# ProProject_ESP32-S3_Brewpiless_V1_Rev_1_.net
KiCad netlist of a schematic drawn in EasyEDA Pro
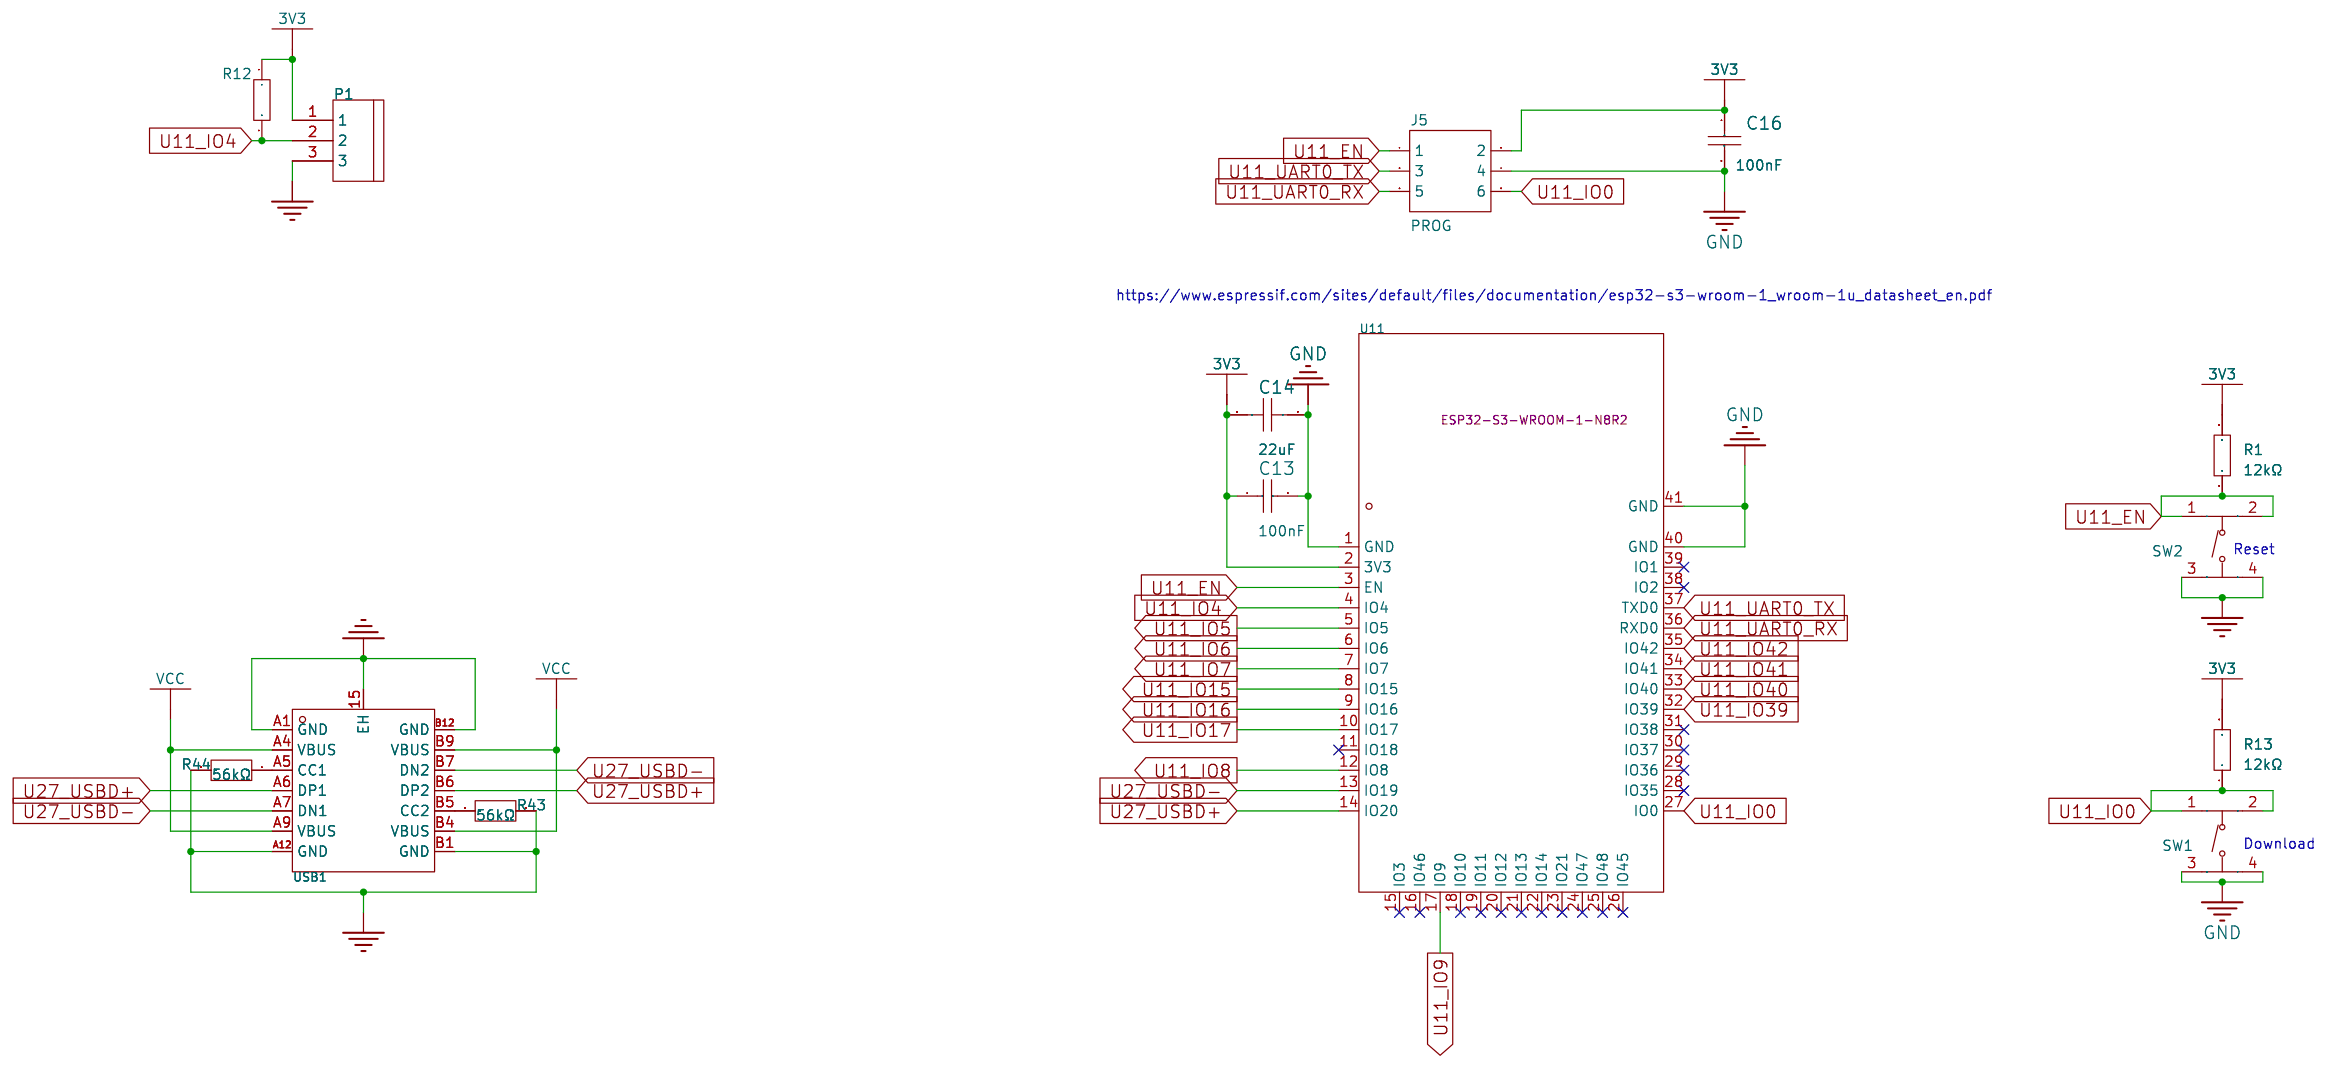
[diagram p0: ESP32]
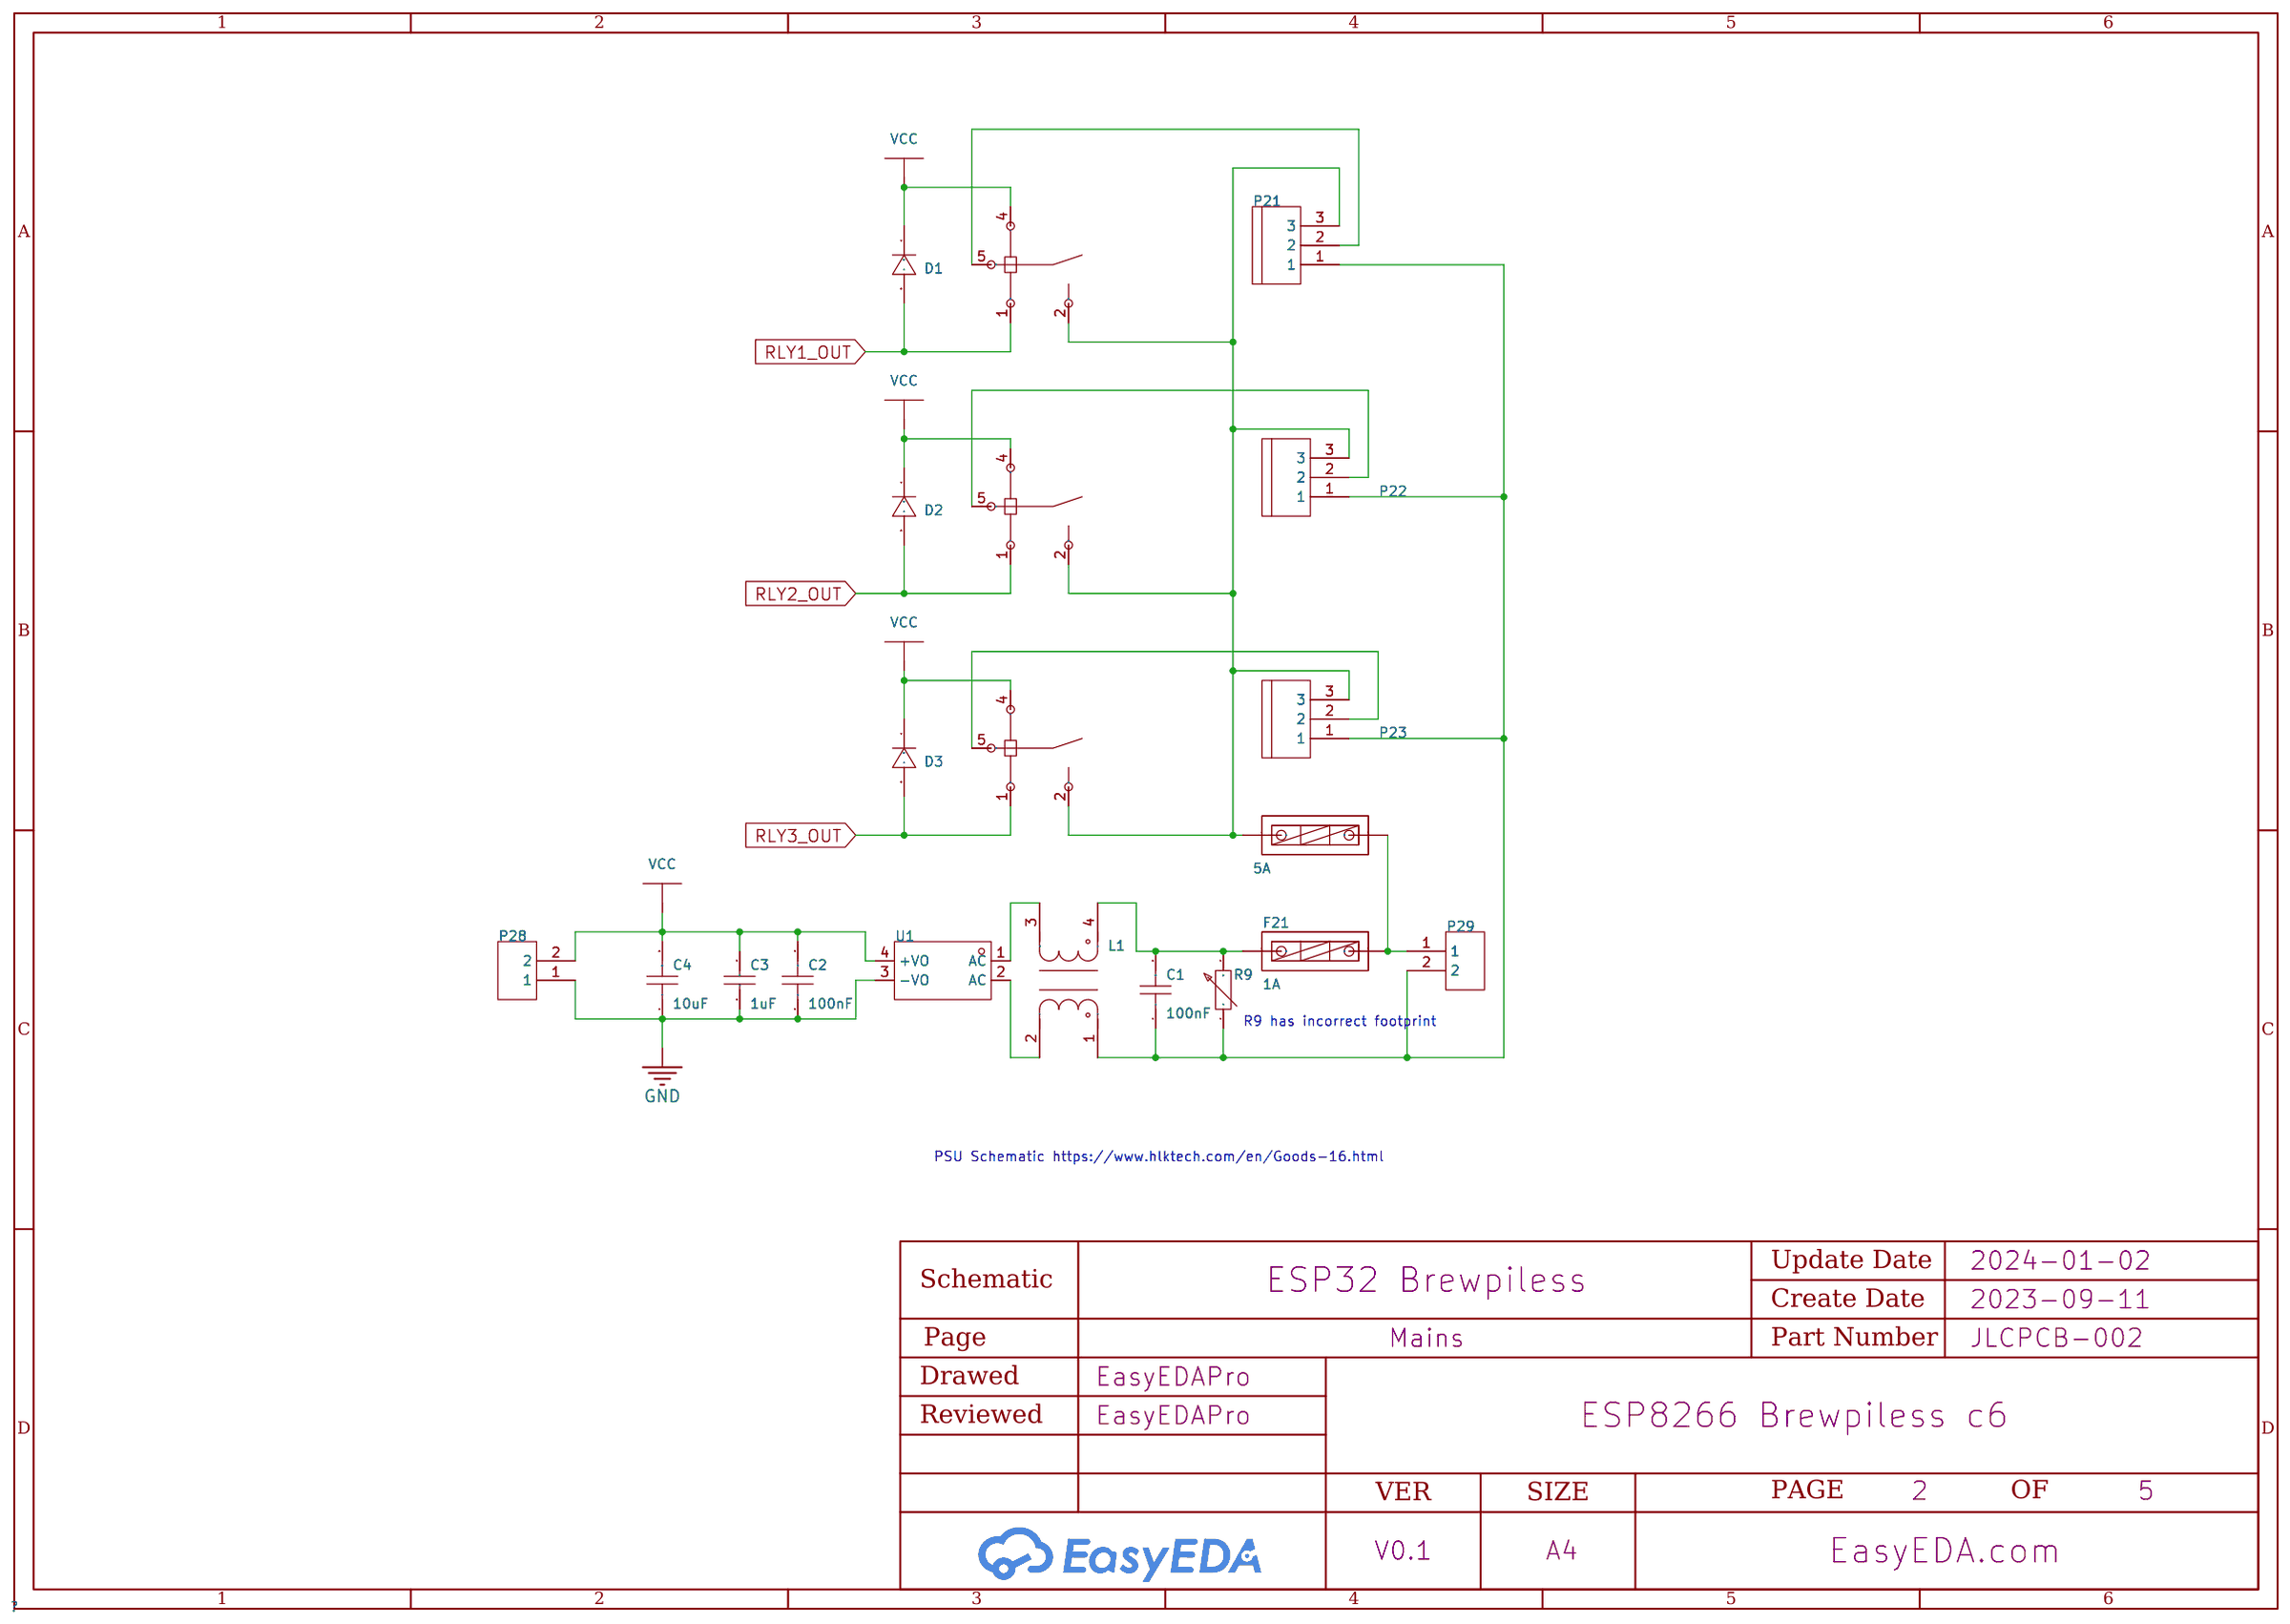
[diagram p1: Mains]
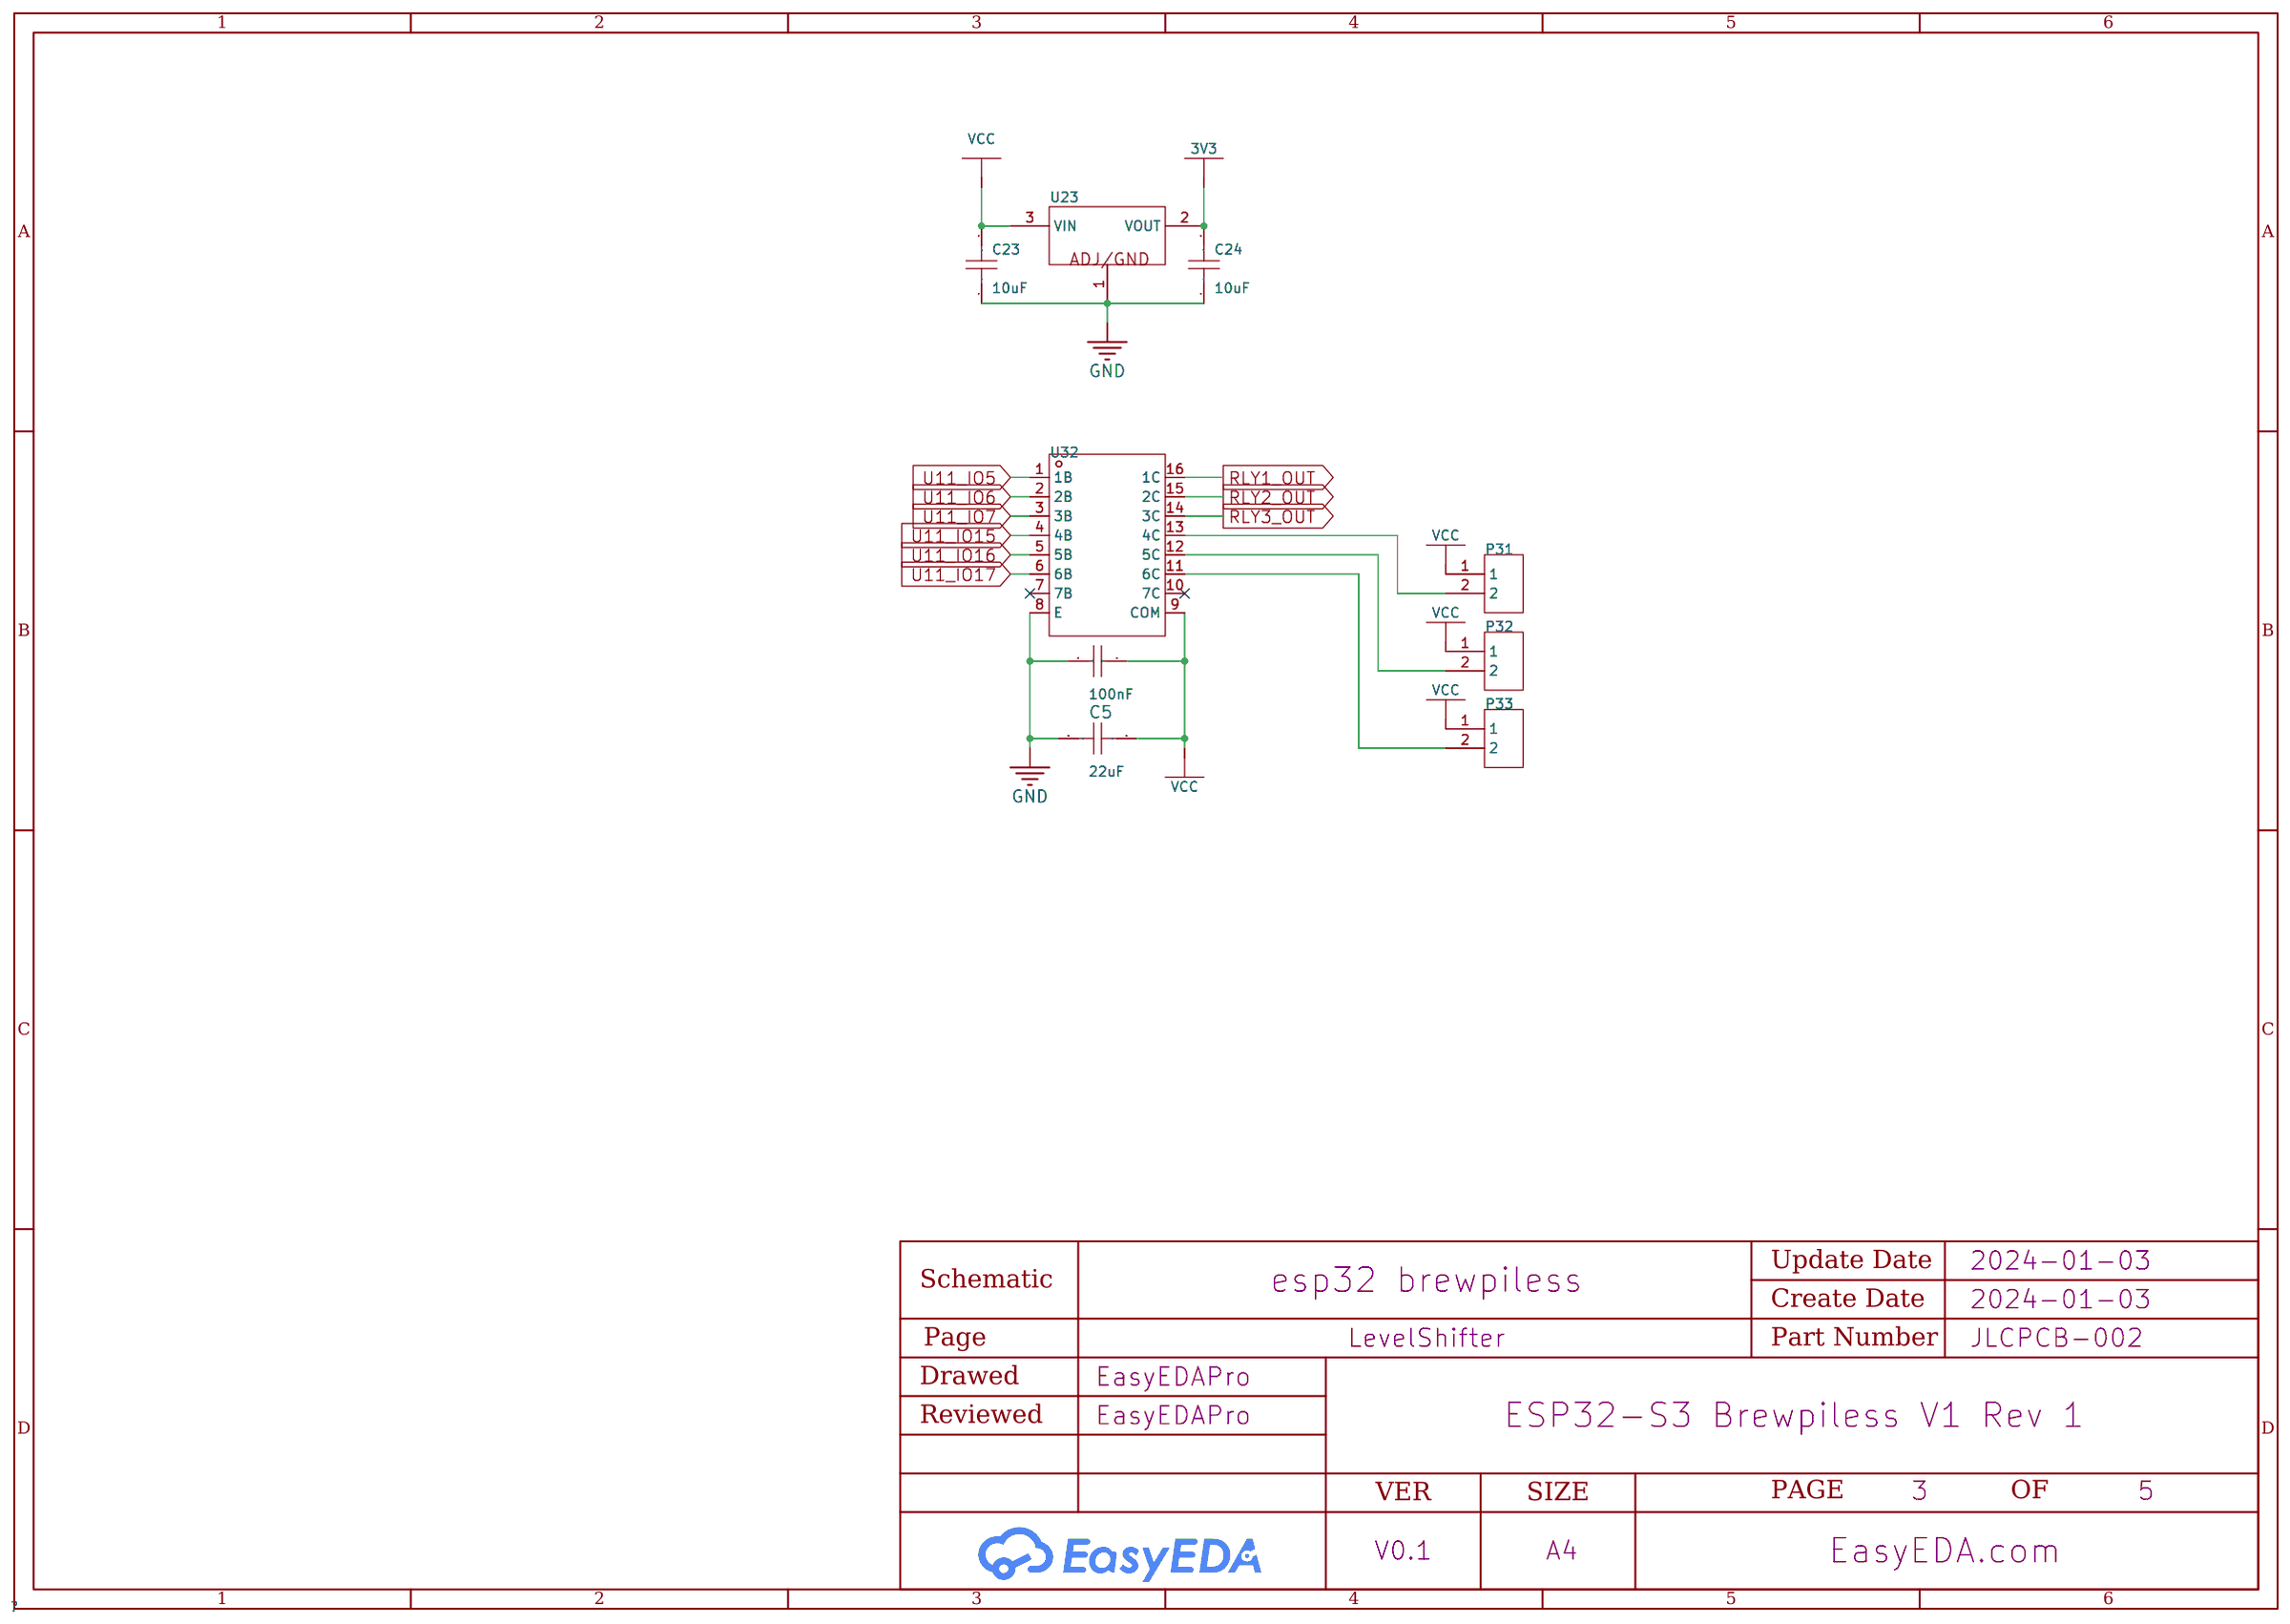
[diagram p2: LevelShifter]
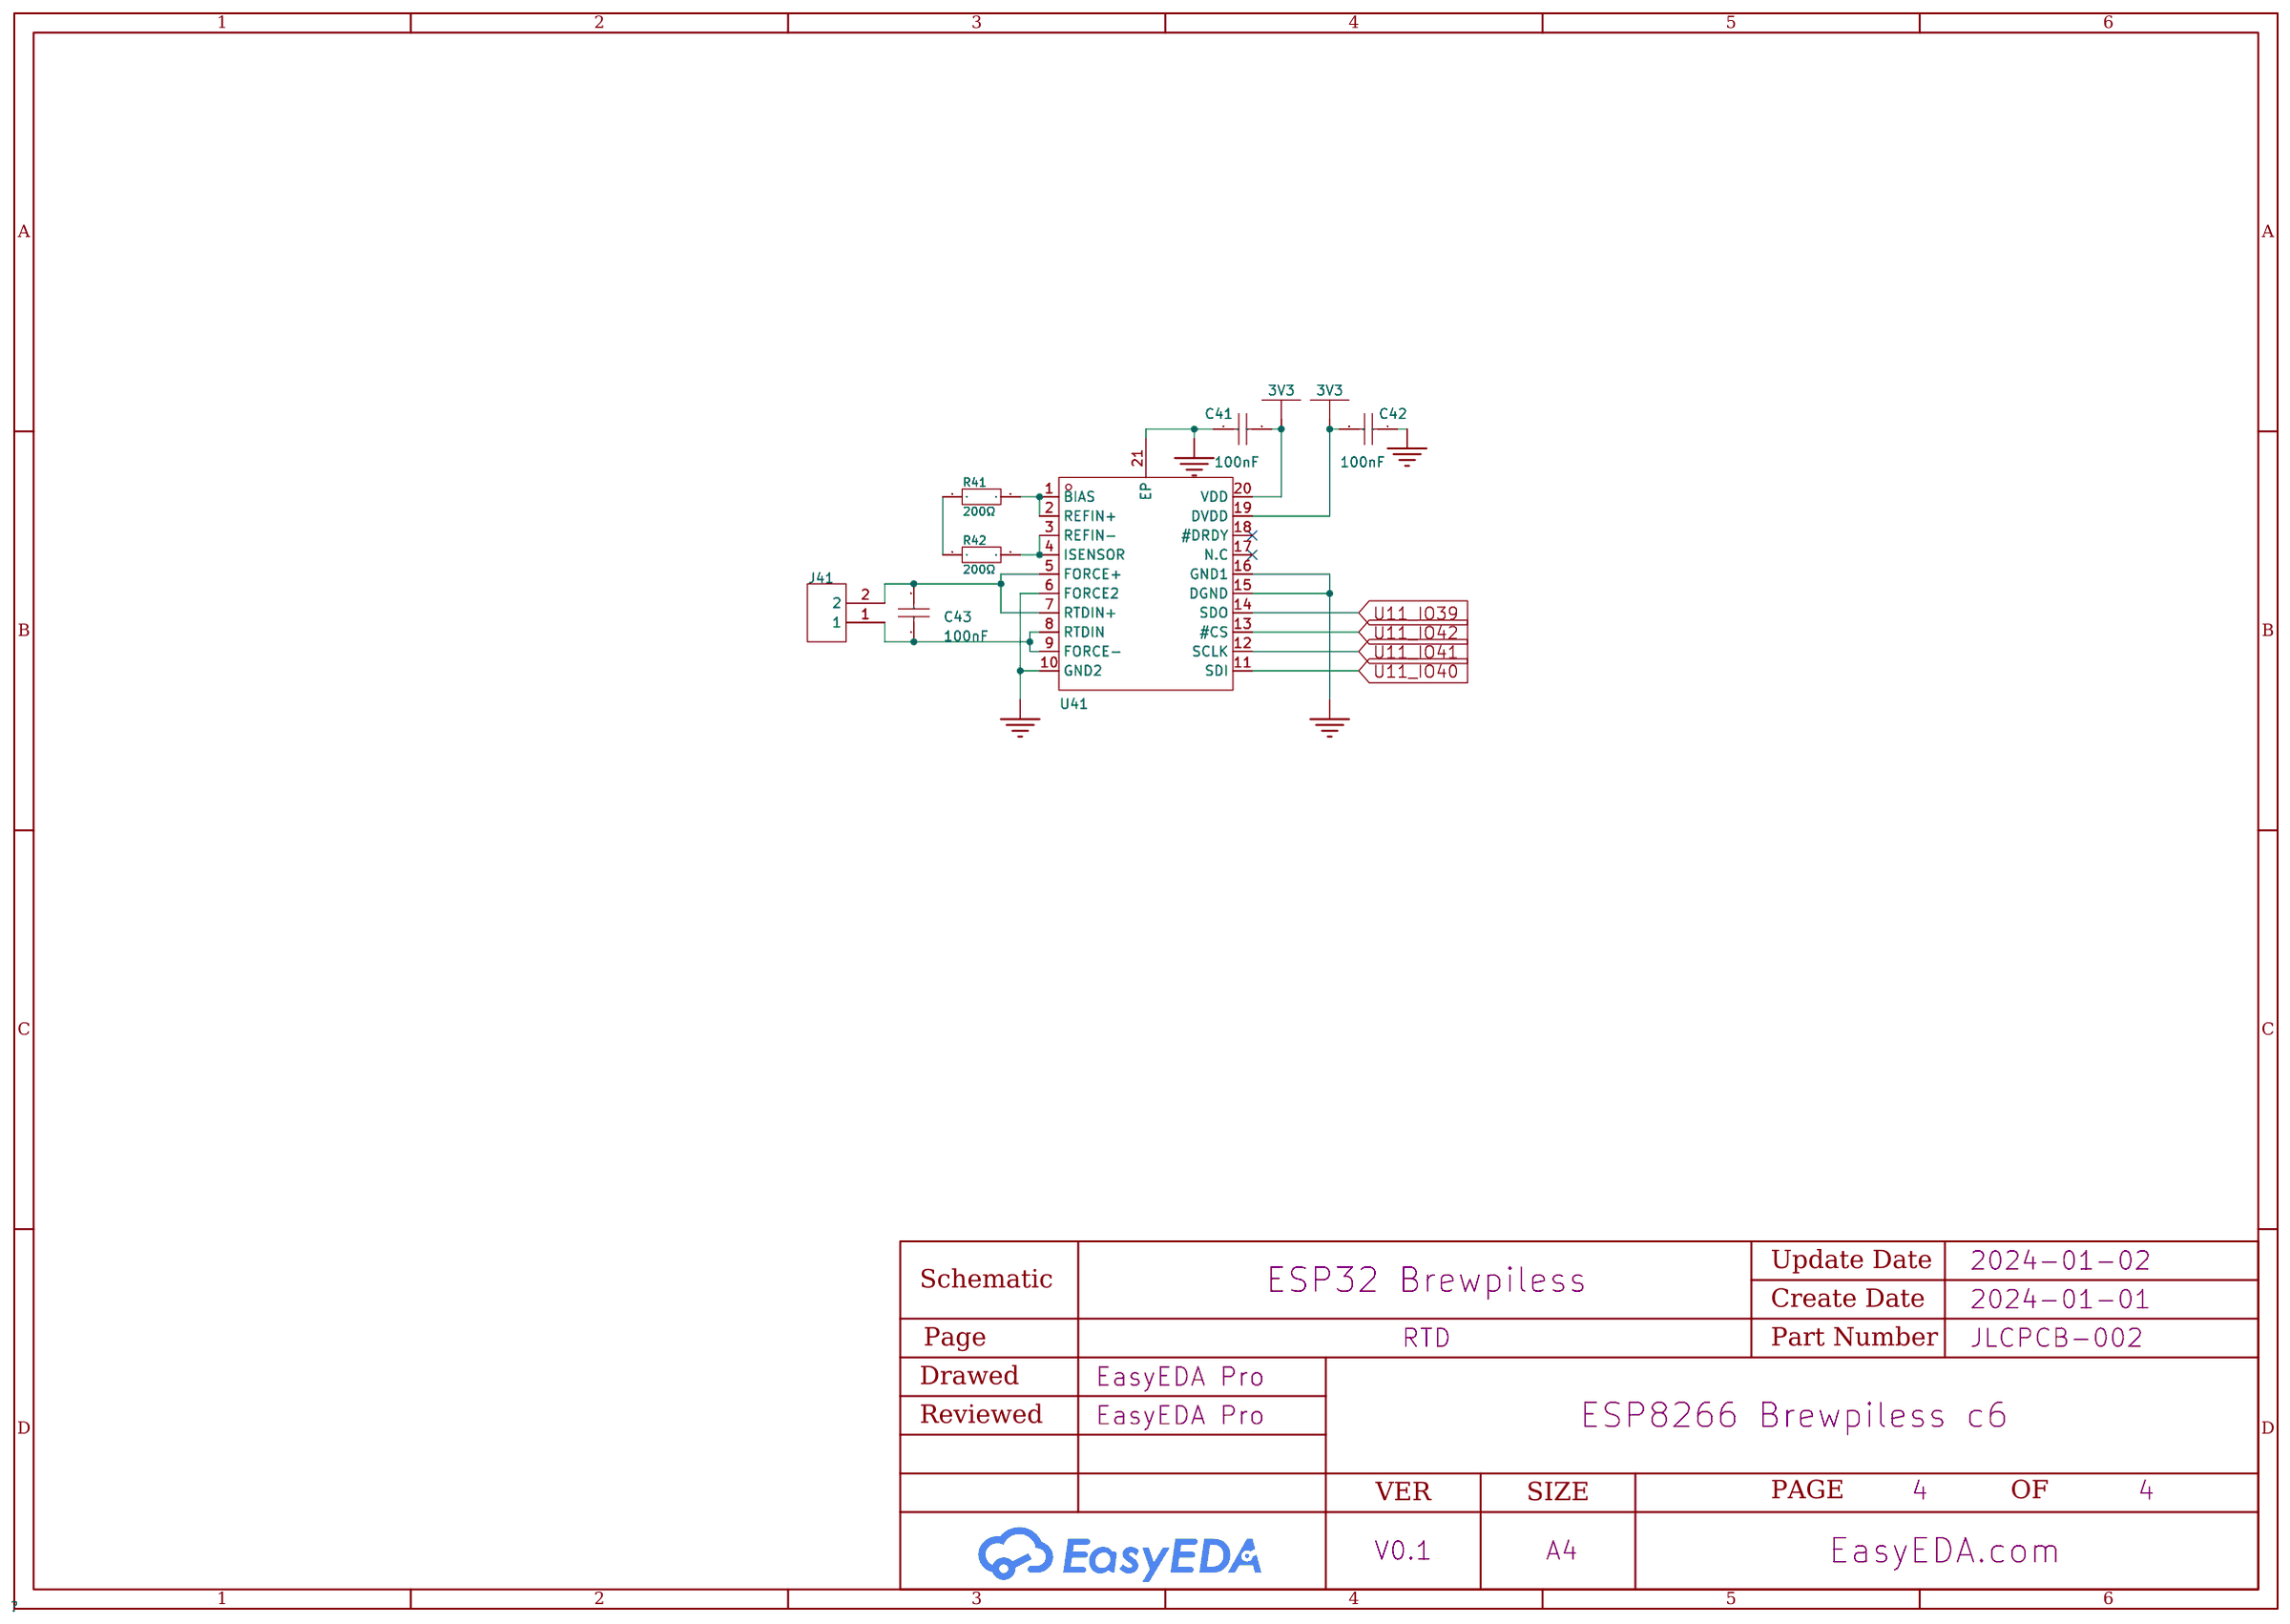
[diagram p3: RTD]
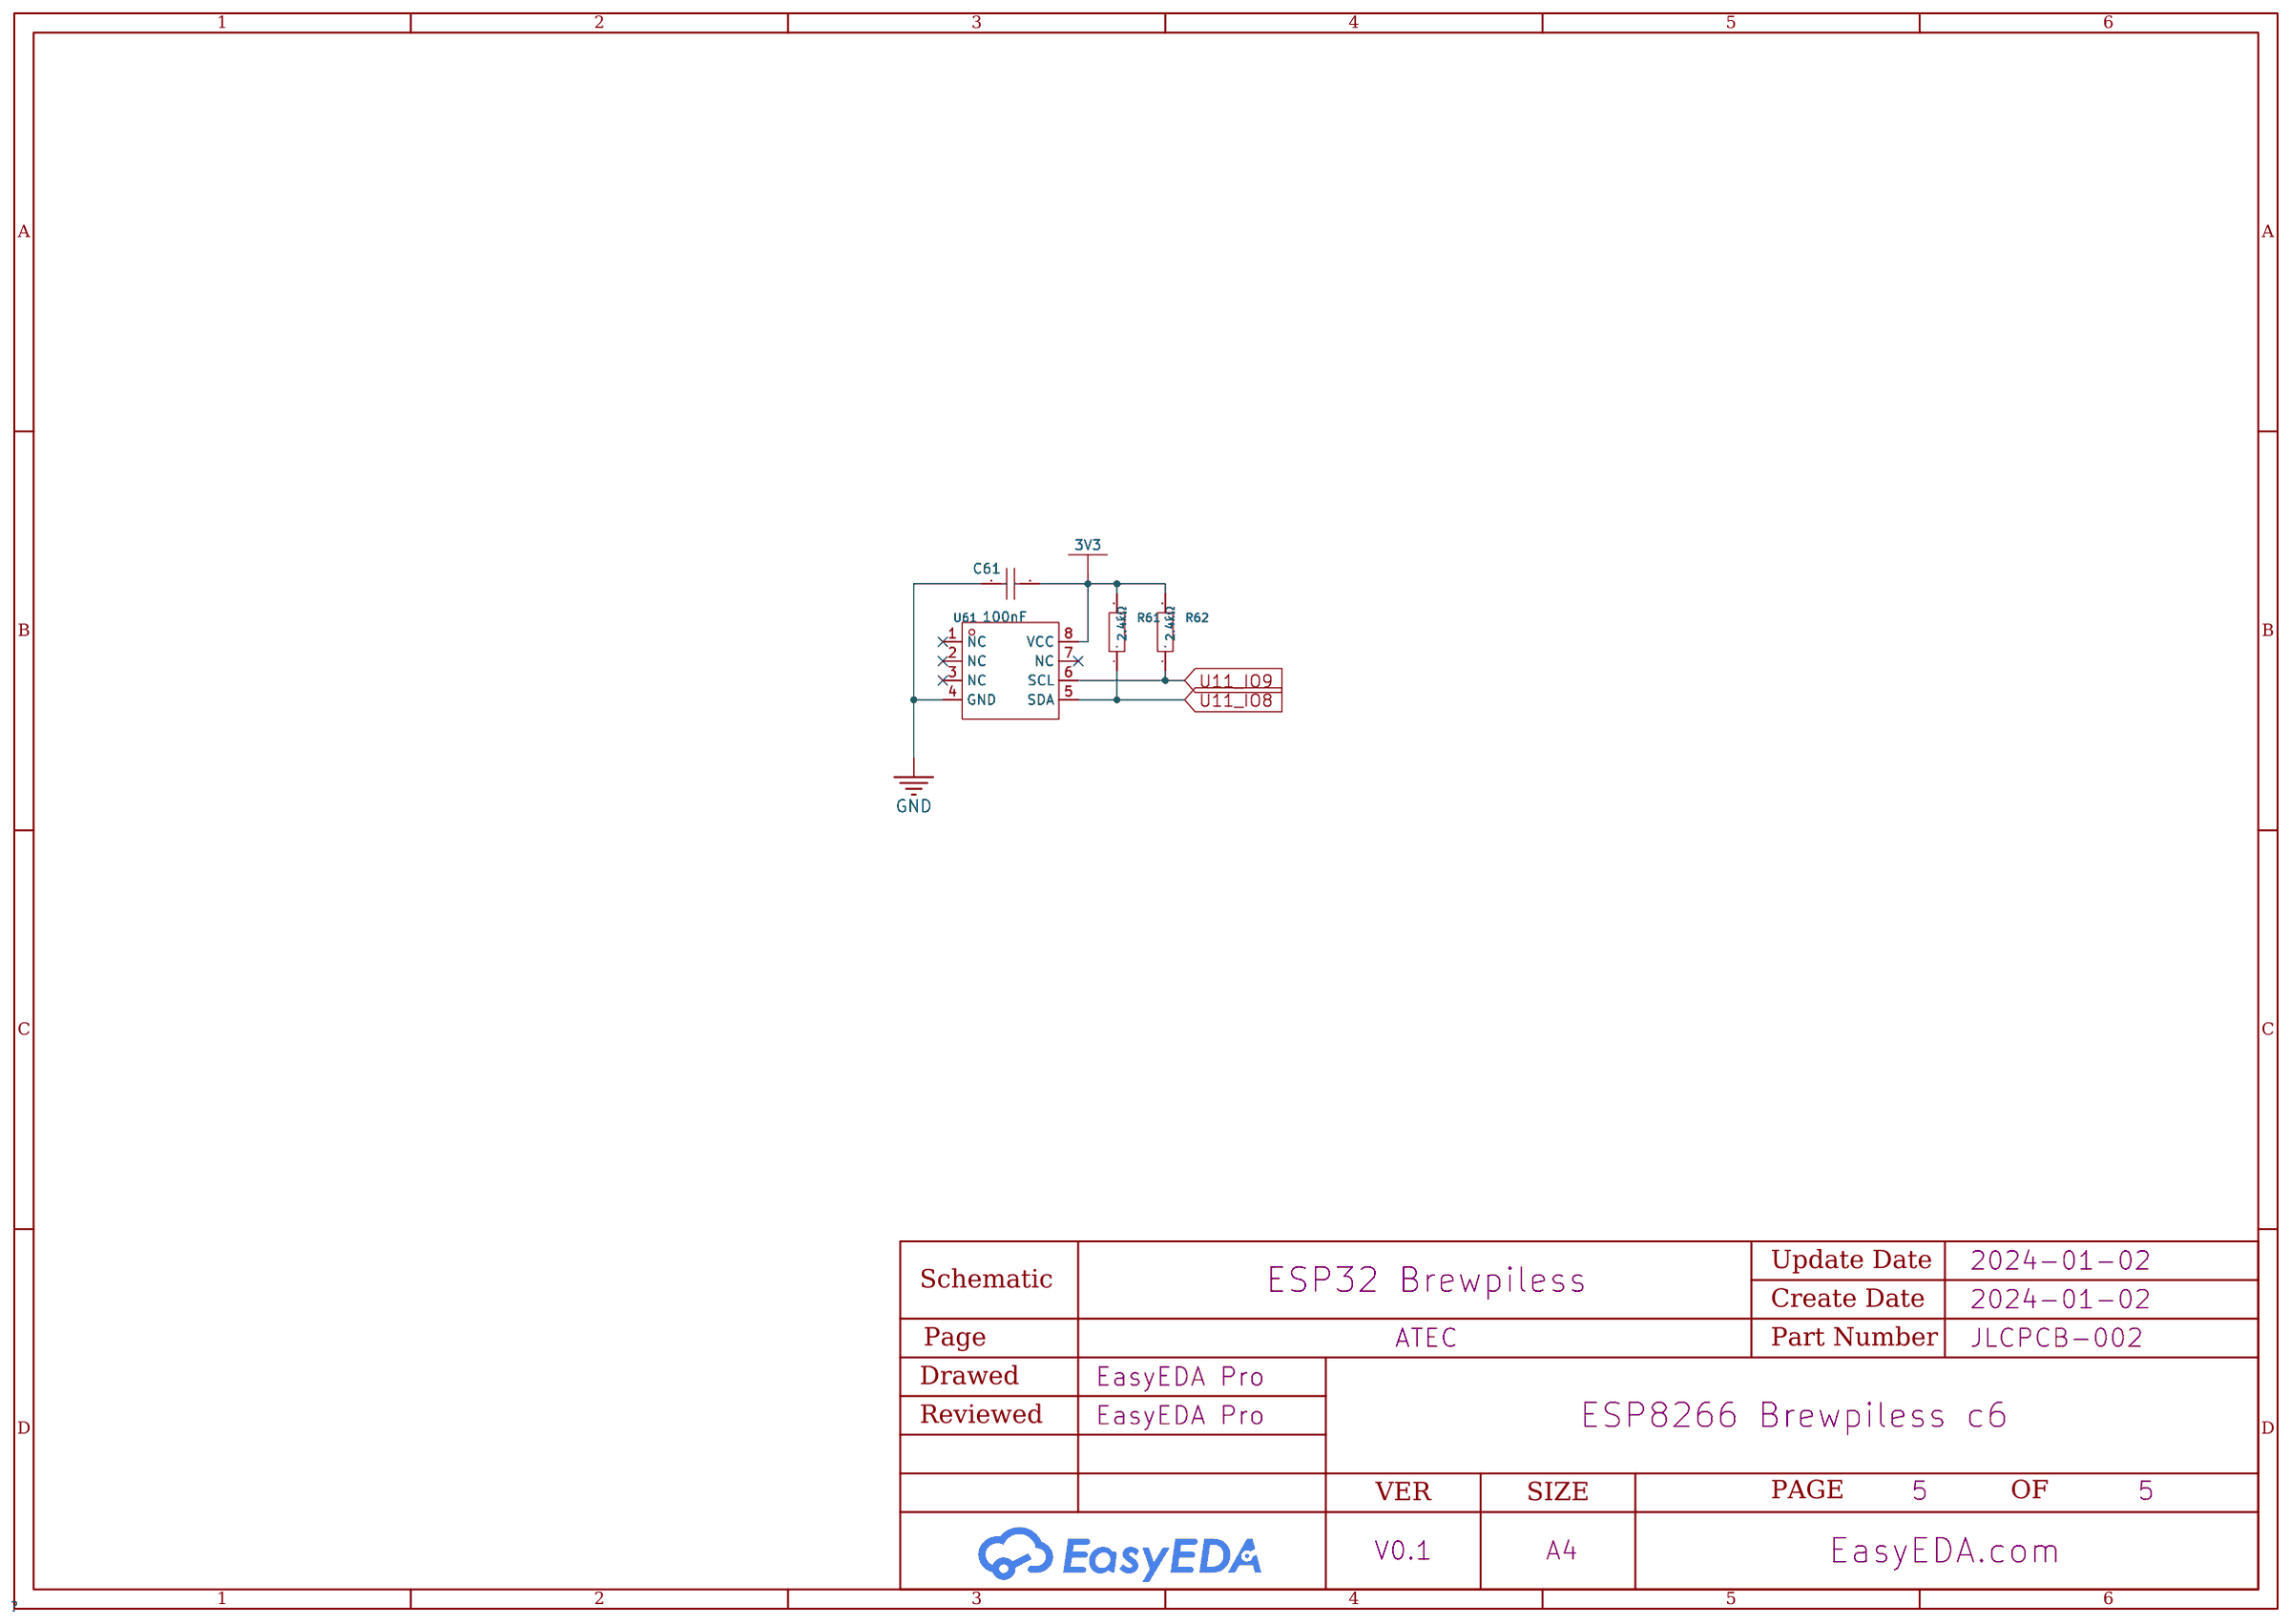
[diagram p4: ATEC]

(export (version "E")
  (design (tool "Eeschema 10.0.6"))
  (components
    (comp (ref "C13")
      (value "100nF")
      (footprint "easyedapro:C0805")
      (fields
        (field (name "Manufacturer Part") "CC0805KRX7R9BB104")
        (field (name "Manufacturer") "YAGEO(国巨)")
      )
      (libsource (lib "easyedapro") (part "CC0805KRX7R9BB104"))
    )
    (comp (ref "C14")
      (value "22uF")
      (footprint "easyedapro:C0805")
      (fields
        (field (name "Manufacturer Part") "CL21A226MAQNNNE")
        (field (name "Manufacturer") "SAMSUNG(三星)")
      )
      (libsource (lib "easyedapro") (part "CL21A226MAQNNNE"))
    )
    (comp (ref "C16")
      (value "100nF")
      (footprint "easyedapro:C0805")
      (fields
        (field (name "Manufacturer Part") "CC0805KRX7R9BB104")
        (field (name "Manufacturer") "YAGEO(国巨)")
      )
      (libsource (lib "easyedapro") (part "CC0805KRX7R9BB104"))
    )
    (comp (ref "J5")
      (value "PROG")
      (footprint "easyedapro:IDC-TH_6P-P2.54_C11214")
      (fields (field (name "Manufacturer Part") "2.54-2*3P简牛") (field (name "Manufacturer") "BOOMELE(博穆精密)"))
      (libsource (lib "easyedapro") (part "HDR-IDC-2.54-2X3P"))
    )
    (comp (ref "P1")
      (value "WJ500V-5.08-3P")
      (footprint "easyedapro:CONN-TH_3P-P5.00_WJ500V-5.08-3P")
      (fields (field (name "Manufacturer") "KANGNEX(康奈克斯电气)"))
      (libsource (lib "easyedapro") (part "WJ500V-5.08-3P-14-00A"))
    )
    (comp (ref "R1")
      (value "12kΩ")
      (footprint "easyedapro:R0805")
      (fields
        (field (name "Manufacturer Part") "0805W8F1202T5E")
        (field (name "Manufacturer") "UNI-ROYAL(厚声)")
      )
      (libsource (lib "easyedapro") (part "0805W8F1202T5E"))
    )
    (comp (ref "R12")
      (value "4.7kΩ")
      (footprint "easyedapro:R0805")
      (fields
        (field (name "Manufacturer Part") "0805W8F4701T5E")
        (field (name "Manufacturer") "UNI-ROYAL(厚声)")
      )
      (libsource (lib "easyedapro") (part "0805W8F4701T5E"))
    )
    (comp (ref "R13")
      (value "12kΩ")
      (footprint "easyedapro:R0805")
      (fields
        (field (name "Manufacturer Part") "0805W8F1202T5E")
        (field (name "Manufacturer") "UNI-ROYAL(厚声)")
      )
      (libsource (lib "easyedapro") (part "0805W8F1202T5E"))
    )
    (comp (ref "R43")
      (value "56kΩ")
      (footprint "easyedapro:R0805")
      (fields (field (name "Manufacturer Part") "ARG05DTC5602") (field (name "Manufacturer") "Viking(光颉)"))
      (libsource (lib "easyedapro") (part "ARG05DTC5602"))
    )
    (comp (ref "R44")
      (value "56kΩ")
      (footprint "easyedapro:R0805")
      (fields (field (name "Manufacturer Part") "ARG05DTC5602") (field (name "Manufacturer") "Viking(光颉)"))
      (libsource (lib "easyedapro") (part "ARG05DTC5602"))
    )
    (comp (ref "SW1")
      (value "TS-1187A-B-A-B")
      (footprint "easyedapro:SW-SMD_4P-L5.1-W5.1-P3.70-LS6.5-TL-2")
      (fields (field (name "Manufacturer") "XKB Connectivity(中国星坤)"))
      (libsource (lib "easyedapro") (part "TS-1187A-B-A-B"))
    )
    (comp (ref "SW2")
      (value "TS-1187A-B-A-B")
      (footprint "easyedapro:SW-SMD_4P-L5.1-W5.1-P3.70-LS6.5-TL-2")
      (fields (field (name "Manufacturer") "XKB Connectivity(中国星坤)"))
      (libsource (lib "easyedapro") (part "TS-1187A-B-A-B"))
    )
    (comp (ref "U11")
      (value "2.4GHz")
      (footprint "easyedapro:WIRELM-SMD_ESP32-S3-WROOM-1")
      (description "Core Processor:ESP32-S3芯片 Support Interface:I2C；GPIO；SPI；PWM；ADC；UART；USB；I2S Frequency:2.4GHz")
      (fields
        (field (name "Manufacturer Part") "ESP32-S3-WROOM-1-N8R2")
        (field (name "Manufacturer") "ESPRESSIF(乐鑫)")
      )
      (libsource (lib "easyedapro") (part "ESP32-S3-WROOM-1(N8R2)"))
    )
    (comp (ref "USB1")
      (value "TYPE-C 14P LTH10.0")
      (footprint "easyedapro:TYPE-C-SMD_918-468K2029Y50001")
      (fields (field (name "Manufacturer") "SHOU HAN(首韩)"))
      (libsource (lib "easyedapro") (part "TYPE-C 14P LTH10.0"))
    )
    (comp (ref "C1")
      (value "100nF")
      (footprint "easyedapro:CAP-TH_L12.0-W5.5-P10.00-D0.6")
      (fields
        (field (name "Manufacturer Part") "MPP104J2W10AJ22620")
        (field (name "Manufacturer") "KNSCHA(科尼盛)")
      )
      (libsource (lib "easyedapro") (part "MPP104J2W10AJ22620"))
    )
    (comp (ref "C2")
      (value "100nF")
      (footprint "easyedapro:CAP-TH_L12.0-W5.5-P10.00-D0.6")
      (fields
        (field (name "Manufacturer Part") "MPP104J2W10AJ22620")
        (field (name "Manufacturer") "KNSCHA(科尼盛)")
      )
      (libsource (lib "easyedapro") (part "MPP104J2W10AJ22620"))
    )
    (comp (ref "C3")
      (value "1uF")
      (footprint "easyedapro:C0805")
      (fields
        (field (name "Manufacturer Part") "CL21B105KBFNNNE")
        (field (name "Manufacturer") "SAMSUNG(三星)")
      )
      (libsource (lib "easyedapro") (part "CL21B105KBFNNNE"))
    )
    (comp (ref "C4")
      (value "10uF")
      (footprint "easyedapro:C0805")
      (fields
        (field (name "Manufacturer Part") "GRM21BR61H106KE43L")
        (field (name "Manufacturer") "muRata(村田)")
      )
      (libsource (lib "easyedapro") (part "GRM21BR61H106KE43L"))
    )
    (comp (ref "D1")
      (value "SM4007PL")
      (footprint "easyedapro:SOD-123F_L2.8-W1.8-LS3.7-RD")
      (fields (field (name "Manufacturer") "MDD"))
      (libsource (lib "easyedapro") (part "SM4007PL"))
    )
    (comp (ref "D2")
      (value "SM4007PL")
      (footprint "easyedapro:SOD-123F_L2.8-W1.8-LS3.7-RD")
      (fields (field (name "Manufacturer") "MDD"))
      (libsource (lib "easyedapro") (part "SM4007PL"))
    )
    (comp (ref "D3")
      (value "SM4007PL")
      (footprint "easyedapro:SOD-123F_L2.8-W1.8-LS3.7-RD")
      (fields (field (name "Manufacturer") "MDD"))
      (libsource (lib "easyedapro") (part "SM4007PL"))
    )
    (comp (ref "F21")
      (value "~")
      (footprint "easyedapro:FUSE-TH_5X20RHOSFUSECLIP-SEAT")
      (fields (field (name "Manufacturer Part") "5x20环保保险管夹/座") (field (name "Manufacturer") "xcfuse(旭程)"))
      (libsource (lib "easyedapro") (part "5x20 RHOS Fuse clip/seat"))
    )
    (comp (ref "F22")
      (value "5A")
      (footprint "easyedapro:FUSE-TH_5X20RHOSFUSECLIP-SEAT")
      (fields (field (name "Manufacturer Part") "5x20环保保险管夹/座") (field (name "Manufacturer") "xcfuse(旭程)"))
      (libsource (lib "easyedapro") (part "5x20 RHOS Fuse clip/seat"))
    )
    (comp (ref "F210")
      (value "1A")
      (footprint "easyedapro:FUSE-TH_5X20RHOSFUSECLIP-SEAT")
      (fields (field (name "Manufacturer Part") "5x20环保保险管夹/座") (field (name "Manufacturer") "xcfuse(旭程)"))
      (libsource (lib "easyedapro") (part "5x20 RHOS Fuse clip/seat"))
    )
    (comp (ref "F220")
      (value "10A")
      (footprint "easyedapro:FUSE-TH_5X20RHOSFUSECLIP-SEAT")
      (fields (field (name "Manufacturer Part") "5x20环保保险管夹/座") (field (name "Manufacturer") "xcfuse(旭程)"))
      (libsource (lib "easyedapro") (part "5x20 RHOS Fuse clip/seat"))
    )
    (comp (ref "K1")
      (value "~")
      (footprint "easyedapro:RELAY-TH_973-XXVDC-SL-A")
      (fields
        (field (name "Manufacturer Part") "973-5VDC-SL-A15A250VAC")
        (field (name "Manufacturer") "NHC(汇龙仓)")
      )
      (libsource (lib "easyedapro") (part "973-5VDC-SL-A 15A250VAC"))
    )
    (comp (ref "K2")
      (value "~")
      (footprint "easyedapro:RELAY-TH_973-XXVDC-SL-A")
      (fields
        (field (name "Manufacturer Part") "973-5VDC-SL-A15A250VAC")
        (field (name "Manufacturer") "NHC(汇龙仓)")
      )
      (libsource (lib "easyedapro") (part "973-5VDC-SL-A 15A250VAC"))
    )
    (comp (ref "K3")
      (value "~")
      (footprint "easyedapro:RELAY-TH_973-XXVDC-SL-A")
      (fields
        (field (name "Manufacturer Part") "973-5VDC-SL-A15A250VAC")
        (field (name "Manufacturer") "NHC(汇龙仓)")
      )
      (libsource (lib "easyedapro") (part "973-5VDC-SL-A 15A250VAC"))
    )
    (comp (ref "L1")
      (value "~")
      (footprint "easyedapro:FILTER-TH_UU10.5Y-10MH")
      (description "Number of Lines:2 Inductance @ Frequency:10mH@1kHz DC Resistance (DCR):750mΩ")
      (fields (field (name "Manufacturer Part") "UU10.5Y-10mH") (field (name "Manufacturer") "FH(风华)"))
      (libsource (lib "easyedapro") (part "UU10.5Y-10mH"))
    )
    (comp (ref "P21")
      (value "WJ500V-5.08-3P")
      (footprint "easyedapro:CONN-TH_3P-P5.00_WJ500V-5.08-3P")
      (fields (field (name "Manufacturer") "KANGNEX(康奈克斯电气)"))
      (libsource (lib "easyedapro") (part "WJ500V-5.08-3P-14-00A"))
    )
    (comp (ref "P22")
      (value "WJ500V-5.08-3P")
      (footprint "easyedapro:CONN-TH_3P-P5.00_WJ500V-5.08-3P")
      (fields (field (name "Manufacturer") "KANGNEX(康奈克斯电气)"))
      (libsource (lib "easyedapro") (part "WJ500V-5.08-3P-14-00A"))
    )
    (comp (ref "P23")
      (value "WJ500V-5.08-3P")
      (footprint "easyedapro:CONN-TH_3P-P5.00_WJ500V-5.08-3P")
      (fields (field (name "Manufacturer") "KANGNEX(康奈克斯电气)"))
      (libsource (lib "easyedapro") (part "WJ500V-5.08-3P-14-00A"))
    )
    (comp (ref "P28")
      (value "WJ500V-5.08-2P")
      (footprint "easyedapro:CONN-TH_2P-P5.00_WJ500V-5.08-2P")
      (fields (field (name "Manufacturer") "KANGNEX(康奈克斯电气)"))
      (libsource (lib "easyedapro") (part "WJ500V-5.08-2P-14-00A"))
    )
    (comp (ref "P29")
      (value "WJ500V-5.08-2P")
      (footprint "easyedapro:CONN-TH_2P-P5.00_WJ500V-5.08-2P")
      (fields (field (name "Manufacturer") "KANGNEX(康奈克斯电气)"))
      (libsource (lib "easyedapro") (part "WJ500V-5.08-2P-14-00A"))
    )
    (comp (ref "R9")
      (value "10D561K")
      (footprint "easyedapro:RES-TH_L13.0-W6.0-P7.50-D0.9-S6.00")
      (fields (field (name "Manufacturer") "HEL(鸿志)"))
      (libsource (lib "easyedapro") (part "10D561K"))
    )
    (comp (ref "U1")
      (value "~")
      (footprint "easyedapro:PWRM-TH_HLK-5M05")
      (fields (field (name "Manufacturer Part") "HLK-5M05") (field (name "Manufacturer") "HI-LINK(海凌科)"))
      (libsource (lib "easyedapro") (part "HLK-5M05"))
    )
    (comp (ref "C5")
      (value "22uF")
      (footprint "easyedapro:C0805")
      (fields
        (field (name "Manufacturer Part") "CL21A226MAQNNNE")
        (field (name "Manufacturer") "SAMSUNG(三星)")
      )
      (libsource (lib "easyedapro") (part "CL21A226MAQNNNE"))
    )
    (comp (ref "C22")
      (value "100nF")
      (footprint "easyedapro:C0805")
      (fields
        (field (name "Manufacturer Part") "CC0805KRX7R9BB104")
        (field (name "Manufacturer") "YAGEO(国巨)")
      )
      (libsource (lib "easyedapro") (part "CC0805KRX7R9BB104"))
    )
    (comp (ref "C23")
      (value "10uF")
      (footprint "easyedapro:C0805")
      (fields
        (field (name "Manufacturer Part") "GRM21BR61H106KE43L")
        (field (name "Manufacturer") "muRata(村田)")
      )
      (libsource (lib "easyedapro") (part "GRM21BR61H106KE43L"))
    )
    (comp (ref "C24")
      (value "10uF")
      (footprint "easyedapro:C0805")
      (fields
        (field (name "Manufacturer Part") "GRM21BR61H106KE43L")
        (field (name "Manufacturer") "muRata(村田)")
      )
      (libsource (lib "easyedapro") (part "GRM21BR61H106KE43L"))
    )
    (comp (ref "P31")
      (value "WJ500V-5.08-2P")
      (footprint "easyedapro:CONN-TH_2P-P5.00_WJ500V-5.08-2P")
      (fields (field (name "Manufacturer") "KANGNEX(康奈克斯电气)"))
      (libsource (lib "easyedapro") (part "WJ500V-5.08-2P-14-00A"))
    )
    (comp (ref "P32")
      (value "WJ500V-5.08-2P")
      (footprint "easyedapro:CONN-TH_2P-P5.00_WJ500V-5.08-2P")
      (fields (field (name "Manufacturer") "KANGNEX(康奈克斯电气)"))
      (libsource (lib "easyedapro") (part "WJ500V-5.08-2P-14-00A"))
    )
    (comp (ref "P33")
      (value "WJ500V-5.08-2P")
      (footprint "easyedapro:CONN-TH_2P-P5.00_WJ500V-5.08-2P")
      (fields (field (name "Manufacturer") "KANGNEX(康奈克斯电气)"))
      (libsource (lib "easyedapro") (part "WJ500V-5.08-2P-14-00A"))
    )
    (comp (ref "U23")
      (value "~")
      (footprint "easyedapro:TO-252-2_L6.6-W6.1-P4.57-LS9.9-TL-CW")
      (fields (field (name "Manufacturer Part") "LM1117RS-3.3") (field (name "Manufacturer") "HTC"))
      (libsource (lib "easyedapro") (part "LM1117RS-3.3"))
    )
    (comp (ref "U32")
      (value "~")
      (footprint "easyedapro:SOIC-16_L9.9-W3.9-P1.27-LS6.0-BL")
      (fields (field (name "Manufacturer Part") "ULN2003ADR") (field (name "Manufacturer") "TI(德州仪器)"))
      (libsource (lib "easyedapro") (part "ULN2003ADR"))
    )
    (comp (ref "C41")
      (value "100nF")
      (footprint "easyedapro:C0805")
      (fields
        (field (name "Manufacturer Part") "CC0805KRX7R9BB104")
        (field (name "Manufacturer") "YAGEO(国巨)")
      )
      (libsource (lib "easyedapro") (part "CC0805KRX7R9BB104"))
    )
    (comp (ref "C42")
      (value "100nF")
      (footprint "easyedapro:C0805")
      (fields
        (field (name "Manufacturer Part") "CC0805KRX7R9BB104")
        (field (name "Manufacturer") "YAGEO(国巨)")
      )
      (libsource (lib "easyedapro") (part "CC0805KRX7R9BB104"))
    )
    (comp (ref "C43")
      (value "100nF")
      (footprint "easyedapro:C0805")
      (fields
        (field (name "Manufacturer Part") "CC0805KRX7R9BB104")
        (field (name "Manufacturer") "YAGEO(国巨)")
      )
      (libsource (lib "easyedapro") (part "CC0805KRX7R9BB104"))
    )
    (comp (ref "J41")
      (value "WJ500V-5.08-2P")
      (footprint "easyedapro:CONN-TH_2P-P5.00_WJ500V-5.08-2P")
      (fields (field (name "Manufacturer") "KANGNEX(康奈克斯电气)"))
      (libsource (lib "easyedapro") (part "WJ500V-5.08-2P-14-00A"))
    )
    (comp (ref "R41")
      (value "200Ω")
      (footprint "easyedapro:R0805")
      (fields
        (field (name "Manufacturer Part") "0805W8F2000T5E")
        (field (name "Manufacturer") "UNI-ROYAL(厚声)")
      )
      (libsource (lib "easyedapro") (part "0805W8F2000T5E"))
    )
    (comp (ref "R42")
      (value "200Ω")
      (footprint "easyedapro:R0805")
      (fields
        (field (name "Manufacturer Part") "0805W8F2000T5E")
        (field (name "Manufacturer") "UNI-ROYAL(厚声)")
      )
      (libsource (lib "easyedapro") (part "0805W8F2000T5E"))
    )
    (comp (ref "U41")
      (value "MAX31865ATP+T")
      (footprint "easyedapro:QFN-20_L5.0-W5.0-P0.65-BL-EP")
      (fields (field (name "Manufacturer") "ADI(亚德诺)"))
      (libsource (lib "easyedapro") (part "MAX31865ATP+T"))
    )
    (comp (ref "C61")
      (value "100nF")
      (footprint "easyedapro:C0805")
      (fields
        (field (name "Manufacturer Part") "CC0805KRX7R9BB104")
        (field (name "Manufacturer") "YAGEO(国巨)")
      )
      (libsource (lib "easyedapro") (part "CC0805KRX7R9BB104"))
    )
    (comp (ref "R61")
      (value "2.4kΩ")
      (footprint "easyedapro:R0805")
      (fields
        (field (name "Manufacturer Part") "0805W8F2401T5E")
        (field (name "Manufacturer") "UNI-ROYAL(厚声)")
      )
      (libsource (lib "easyedapro") (part "0805W8F2401T5E"))
    )
    (comp (ref "R62")
      (value "2.4kΩ")
      (footprint "easyedapro:R0805")
      (fields
        (field (name "Manufacturer Part") "0805W8F2401T5E")
        (field (name "Manufacturer") "UNI-ROYAL(厚声)")
      )
      (libsource (lib "easyedapro") (part "0805W8F2401T5E"))
    )
    (comp (ref "U61")
      (value "ATECC608A-SSHDA-T")
      (footprint "easyedapro:SOIC-8_L4.9-W3.9-P1.27-LS6.0-BL")
      (fields (field (name "Manufacturer") "MICROCHIP(美国微芯)"))
      (libsource (lib "easyedapro") (part "ATECC608A-SSHDA-T_C616024"))
    )
  )
  (nets
    (net (code "1") (name "3V3") (class "Default")
      (node (ref "C13") (pin "1") (pinfunction "1_1") (pintype "input"))
      (node (ref "C14") (pin "2") (pinfunction "2_2") (pintype "input"))
      (node (ref "C16") (pin "1") (pinfunction "1_1") (pintype "input"))
      (node (ref "C24") (pin "2") (pinfunction "2_2") (pintype "input"))
      (node (ref "C41") (pin "2") (pinfunction "2_2") (pintype "input"))
      (node (ref "C42") (pin "2") (pinfunction "2_2") (pintype "input"))
      (node (ref "C61") (pin "2") (pinfunction "2_2") (pintype "input"))
      (node (ref "J5") (pin "2") (pinfunction "2_2") (pintype "input"))
      (node (ref "P1") (pin "1") (pinfunction "1_1") (pintype "input"))
      (node (ref "R1") (pin "2") (pinfunction "2_2") (pintype "input"))
      (node (ref "R12") (pin "1") (pinfunction "1_1") (pintype "input"))
      (node (ref "R13") (pin "2") (pinfunction "2_2") (pintype "input"))
      (node (ref "R61") (pin "2") (pinfunction "2_2") (pintype "input"))
      (node (ref "R62") (pin "2") (pinfunction "2_2") (pintype "input"))
      (node (ref "U11") (pin "2") (pinfunction "3V3_2") (pintype "input"))
      (node (ref "U23") (pin "2") (pinfunction "VOUT_2") (pintype "input"))
      (node (ref "U41") (pin "19") (pinfunction "DVDD_19") (pintype "input"))
      (node (ref "U41") (pin "20") (pinfunction "VDD_20") (pintype "input"))
      (node (ref "U61") (pin "8") (pinfunction "VCC_8") (pintype "input"))
    )
    (net (code "2") (name "GND") (class "Default")
      (node (ref "C13") (pin "2") (pinfunction "2_2") (pintype "input"))
      (node (ref "C14") (pin "1") (pinfunction "1_1") (pintype "input"))
      (node (ref "C16") (pin "2") (pinfunction "2_2") (pintype "input"))
      (node (ref "C2") (pin "1") (pinfunction "1_1") (pintype "input"))
      (node (ref "C22") (pin "2") (pinfunction "2_2") (pintype "input"))
      (node (ref "C23") (pin "1") (pinfunction "1_1") (pintype "input"))
      (node (ref "C24") (pin "1") (pinfunction "1_1") (pintype "input"))
      (node (ref "C3") (pin "1") (pinfunction "1_1") (pintype "input"))
      (node (ref "C4") (pin "1") (pinfunction "1_1") (pintype "input"))
      (node (ref "C41") (pin "1") (pinfunction "1_1") (pintype "input"))
      (node (ref "C42") (pin "1") (pinfunction "1_1") (pintype "input"))
      (node (ref "C5") (pin "2") (pinfunction "2_2") (pintype "input"))
      (node (ref "C61") (pin "1") (pinfunction "1_1") (pintype "input"))
      (node (ref "J5") (pin "4") (pinfunction "4_4") (pintype "input"))
      (node (ref "P1") (pin "3") (pinfunction "3_3") (pintype "input"))
      (node (ref "P28") (pin "1") (pinfunction "1_1") (pintype "input"))
      (node (ref "R43") (pin "1") (pinfunction "1_1") (pintype "input"))
      (node (ref "R44") (pin "2") (pinfunction "2_2") (pintype "input"))
      (node (ref "SW1") (pin "3") (pinfunction "C_3") (pintype "input"))
      (node (ref "SW1") (pin "4") (pinfunction "D_4") (pintype "input"))
      (node (ref "SW2") (pin "3") (pinfunction "C_3") (pintype "input"))
      (node (ref "SW2") (pin "4") (pinfunction "D_4") (pintype "input"))
      (node (ref "U1") (pin "3") (pinfunction "-VO_3") (pintype "input"))
      (node (ref "U11") (pin "1") (pinfunction "GND_1") (pintype "input"))
      (node (ref "U11") (pin "40") (pinfunction "GND_40") (pintype "input"))
      (node (ref "U11") (pin "41") (pinfunction "GND_41") (pintype "input"))
      (node (ref "U23") (pin "1") (pinfunction "ADJ_1") (pintype "input"))
      (node (ref "U32") (pin "8") (pinfunction "E_8") (pintype "input"))
      (node (ref "U41") (pin "10") (pinfunction "GND2_10") (pintype "input"))
      (node (ref "U41") (pin "15") (pinfunction "DGND_15") (pintype "input"))
      (node (ref "U41") (pin "16") (pinfunction "GND1_16") (pintype "input"))
      (node (ref "U41") (pin "21") (pinfunction "EP_21") (pintype "input"))
      (node (ref "U41") (pin "6") (pinfunction "FORCE2_6") (pintype "input"))
      (node (ref "U61") (pin "4") (pinfunction "GND_4") (pintype "input"))
      (node (ref "USB1") (pin "15") (pinfunction "EH_15") (pintype "input"))
      (node (ref "USB1") (pin "A1") (pinfunction "GND_A1") (pintype "input"))
      (node (ref "USB1") (pin "A12") (pinfunction "GND_A12") (pintype "input"))
      (node (ref "USB1") (pin "B1") (pinfunction "GND_B1") (pintype "input"))
      (node (ref "USB1") (pin "B12") (pinfunction "GND_B12") (pintype "input"))
    )
    (net (code "3") (name "Net-(C1-Pad1)") (class "Default")
      (node (ref "C1") (pin "1") (pinfunction "1_1") (pintype "input"))
      (node (ref "L1") (pin "1") (pinfunction "1_1") (pintype "input"))
      (node (ref "P21") (pin "1") (pinfunction "1_1") (pintype "input"))
      (node (ref "P22") (pin "1") (pinfunction "1_1") (pintype "input"))
      (node (ref "P23") (pin "1") (pinfunction "1_1") (pintype "input"))
      (node (ref "P29") (pin "2") (pinfunction "2_2") (pintype "input"))
      (node (ref "R9") (pin "1") (pinfunction "1_1") (pintype "input"))
    )
    (net (code "4") (name "Net-(C1-Pad2)") (class "Default")
      (node (ref "C1") (pin "2") (pinfunction "2_2") (pintype "input"))
      (node (ref "F21") (pin "1") (pinfunction "1_1") (pintype "input"))
      (node (ref "L1") (pin "4") (pinfunction "4_4") (pintype "input"))
      (node (ref "R9") (pin "2") (pinfunction "2_2") (pintype "input"))
    )
    (net (code "5") (name "Net-(F22-Pad1)") (class "Default")
      (node (ref "F22") (pin "1") (pinfunction "1_1") (pintype "input"))
      (node (ref "K1") (pin "2") (pinfunction "2_2") (pintype "input"))
      (node (ref "K2") (pin "2") (pinfunction "2_2") (pintype "input"))
      (node (ref "K3") (pin "2") (pinfunction "2_2") (pintype "input"))
      (node (ref "P21") (pin "3") (pinfunction "3_3") (pintype "input"))
      (node (ref "P22") (pin "3") (pinfunction "3_3") (pintype "input"))
      (node (ref "P23") (pin "3") (pinfunction "3_3") (pintype "input"))
    )
    (net (code "6") (name "Net-(F210-Pad1)") (class "Default")
      (node (ref "F210") (pin "1") (pinfunction "1_1") (pintype "input"))
      (node (ref "F220") (pin "1") (pinfunction "1_1") (pintype "input"))
      (node (ref "P29") (pin "1") (pinfunction "1_1") (pintype "input"))
    )
    (net (code "7") (name "Net-(K1-Pad5)") (class "Default")
      (node (ref "K1") (pin "5") (pinfunction "5_5") (pintype "input"))
      (node (ref "P21") (pin "2") (pinfunction "2_2") (pintype "input"))
    )
    (net (code "8") (name "Net-(K2-Pad5)") (class "Default")
      (node (ref "K2") (pin "5") (pinfunction "5_5") (pintype "input"))
      (node (ref "P22") (pin "2") (pinfunction "2_2") (pintype "input"))
    )
    (net (code "9") (name "Net-(K3-Pad5)") (class "Default")
      (node (ref "K3") (pin "5") (pinfunction "5_5") (pintype "input"))
      (node (ref "P23") (pin "2") (pinfunction "2_2") (pintype "input"))
    )
    (net (code "10") (name "Net-(L1-Pad2)") (class "Default")
      (node (ref "L1") (pin "2") (pinfunction "2_2") (pintype "input"))
      (node (ref "U1") (pin "2") (pinfunction "AC_2") (pintype "input"))
    )
    (net (code "11") (name "Net-(L1-Pad3)") (class "Default")
      (node (ref "L1") (pin "3") (pinfunction "3_3") (pintype "input"))
      (node (ref "U1") (pin "1") (pinfunction "AC_1") (pintype "input"))
    )
    (net (code "12") (name "Net-(R41-Pad2)") (class "Default")
      (node (ref "R41") (pin "2") (pinfunction "2_2") (pintype "input"))
      (node (ref "R42") (pin "2") (pinfunction "2_2") (pintype "input"))
    )
    (net (code "13") (name "Net-(U32-4C)") (class "Default")
      (node (ref "P31") (pin "2") (pinfunction "2_2") (pintype "input"))
      (node (ref "U32") (pin "13") (pinfunction "4C_13") (pintype "input"))
    )
    (net (code "14") (name "Net-(U32-5C)") (class "Default")
      (node (ref "P32") (pin "2") (pinfunction "2_2") (pintype "input"))
      (node (ref "U32") (pin "12") (pinfunction "5C_12") (pintype "input"))
    )
    (net (code "15") (name "Net-(U32-6C)") (class "Default")
      (node (ref "P33") (pin "2") (pinfunction "2_2") (pintype "input"))
      (node (ref "U32") (pin "11") (pinfunction "6C_11") (pintype "input"))
    )
    (net (code "16") (name "Net-(U41-BIAS)") (class "Default")
      (node (ref "R41") (pin "1") (pinfunction "1_1") (pintype "input"))
      (node (ref "U41") (pin "1") (pinfunction "BIAS_1") (pintype "input"))
      (node (ref "U41") (pin "2") (pinfunction "REFIN+_2") (pintype "input"))
    )
    (net (code "17") (name "Net-(U41-FORCE+)") (class "Default")
      (node (ref "C43") (pin "2") (pinfunction "2_2") (pintype "input"))
      (node (ref "J41") (pin "2") (pinfunction "2_2") (pintype "input"))
      (node (ref "U41") (pin "5") (pinfunction "FORCE+_5") (pintype "input"))
      (node (ref "U41") (pin "7") (pinfunction "RTDIN+_7") (pintype "input"))
    )
    (net (code "18") (name "Net-(U41-FORCE-)") (class "Default")
      (node (ref "C43") (pin "1") (pinfunction "1_1") (pintype "input"))
      (node (ref "J41") (pin "1") (pinfunction "1_1") (pintype "input"))
      (node (ref "U41") (pin "8") (pinfunction "RTDIN_8") (pintype "input"))
      (node (ref "U41") (pin "9") (pinfunction "FORCE-_9") (pintype "input"))
    )
    (net (code "19") (name "Net-(U41-ISENSOR)") (class "Default")
      (node (ref "R42") (pin "1") (pinfunction "1_1") (pintype "input"))
      (node (ref "U41") (pin "3") (pinfunction "REFIN-_3") (pintype "input"))
      (node (ref "U41") (pin "4") (pinfunction "ISENSOR_4") (pintype "input"))
    )
    (net (code "20") (name "Net-(USB1-CC1)") (class "Default")
      (node (ref "R44") (pin "1") (pinfunction "1_1") (pintype "input"))
      (node (ref "USB1") (pin "A5") (pinfunction "CC1_A5") (pintype "input"))
    )
    (net (code "21") (name "Net-(USB1-CC2)") (class "Default")
      (node (ref "R43") (pin "2") (pinfunction "2_2") (pintype "input"))
      (node (ref "USB1") (pin "B5") (pinfunction "CC2_B5") (pintype "input"))
    )
    (net (code "22") (name "RLY1_OUT") (class "Default")
      (node (ref "D1") (pin "2") (pinfunction "A_2") (pintype "input"))
      (node (ref "K1") (pin "1") (pinfunction "1_1") (pintype "input"))
      (node (ref "U32") (pin "16") (pinfunction "1C_16") (pintype "input"))
    )
    (net (code "23") (name "RLY2_OUT") (class "Default")
      (node (ref "D2") (pin "2") (pinfunction "A_2") (pintype "input"))
      (node (ref "K2") (pin "1") (pinfunction "1_1") (pintype "input"))
      (node (ref "U32") (pin "15") (pinfunction "2C_15") (pintype "input"))
    )
    (net (code "24") (name "RLY3_OUT") (class "Default")
      (node (ref "D3") (pin "2") (pinfunction "A_2") (pintype "input"))
      (node (ref "K3") (pin "1") (pinfunction "1_1") (pintype "input"))
      (node (ref "U32") (pin "14") (pinfunction "3C_14") (pintype "input"))
    )
    (net (code "25") (name "U11_EN") (class "Default")
      (node (ref "J5") (pin "1") (pinfunction "1_1") (pintype "input"))
      (node (ref "R1") (pin "1") (pinfunction "1_1") (pintype "input"))
      (node (ref "SW2") (pin "1") (pinfunction "A_1") (pintype "input"))
      (node (ref "SW2") (pin "2") (pinfunction "B_2") (pintype "input"))
      (node (ref "U11") (pin "3") (pinfunction "EN_3") (pintype "input"))
    )
    (net (code "26") (name "U11_IO0") (class "Default")
      (node (ref "J5") (pin "6") (pinfunction "6_6") (pintype "input"))
      (node (ref "R13") (pin "1") (pinfunction "1_1") (pintype "input"))
      (node (ref "SW1") (pin "1") (pinfunction "A_1") (pintype "input"))
      (node (ref "SW1") (pin "2") (pinfunction "B_2") (pintype "input"))
      (node (ref "U11") (pin "27") (pinfunction "IO0_27") (pintype "input"))
    )
    (net (code "27") (name "U11_IO4") (class "Default")
      (node (ref "P1") (pin "2") (pinfunction "2_2") (pintype "input"))
      (node (ref "R12") (pin "2") (pinfunction "2_2") (pintype "input"))
      (node (ref "U11") (pin "4") (pinfunction "IO4_4") (pintype "input"))
    )
    (net (code "28") (name "U11_IO5") (class "Default")
      (node (ref "U11") (pin "5") (pinfunction "IO5_5") (pintype "input"))
      (node (ref "U32") (pin "1") (pinfunction "1B_1") (pintype "input"))
    )
    (net (code "29") (name "U11_IO6") (class "Default")
      (node (ref "U11") (pin "6") (pinfunction "IO6_6") (pintype "input"))
      (node (ref "U32") (pin "2") (pinfunction "2B_2") (pintype "input"))
    )
    (net (code "30") (name "U11_IO7") (class "Default")
      (node (ref "U11") (pin "7") (pinfunction "IO7_7") (pintype "input"))
      (node (ref "U32") (pin "3") (pinfunction "3B_3") (pintype "input"))
    )
    (net (code "31") (name "U11_IO8") (class "Default")
      (node (ref "R61") (pin "1") (pinfunction "1_1") (pintype "input"))
      (node (ref "U11") (pin "12") (pinfunction "IO8_12") (pintype "input"))
      (node (ref "U61") (pin "5") (pinfunction "SDA_5") (pintype "input"))
    )
    (net (code "32") (name "U11_IO9") (class "Default")
      (node (ref "R62") (pin "1") (pinfunction "1_1") (pintype "input"))
      (node (ref "U11") (pin "17") (pinfunction "IO9_17") (pintype "input"))
      (node (ref "U61") (pin "6") (pinfunction "SCL_6") (pintype "input"))
    )
    (net (code "33") (name "U11_IO15") (class "Default")
      (node (ref "U11") (pin "8") (pinfunction "IO15_8") (pintype "input"))
      (node (ref "U32") (pin "4") (pinfunction "4B_4") (pintype "input"))
    )
    (net (code "34") (name "U11_IO16") (class "Default")
      (node (ref "U11") (pin "9") (pinfunction "IO16_9") (pintype "input"))
      (node (ref "U32") (pin "5") (pinfunction "5B_5") (pintype "input"))
    )
    (net (code "35") (name "U11_IO17") (class "Default")
      (node (ref "U11") (pin "10") (pinfunction "IO17_10") (pintype "input"))
      (node (ref "U32") (pin "6") (pinfunction "6B_6") (pintype "input"))
    )
    (net (code "36") (name "U11_IO39") (class "Default")
      (node (ref "U11") (pin "32") (pinfunction "IO39_32") (pintype "input"))
      (node (ref "U41") (pin "14") (pinfunction "SDO_14") (pintype "input"))
    )
    (net (code "37") (name "U11_IO40") (class "Default")
      (node (ref "U11") (pin "33") (pinfunction "IO40_33") (pintype "input"))
      (node (ref "U41") (pin "11") (pinfunction "SDI_11") (pintype "input"))
    )
    (net (code "38") (name "U11_IO41") (class "Default")
      (node (ref "U11") (pin "34") (pinfunction "IO41_34") (pintype "input"))
      (node (ref "U41") (pin "12") (pinfunction "SCLK_12") (pintype "input"))
    )
    (net (code "39") (name "U11_IO42") (class "Default")
      (node (ref "U11") (pin "35") (pinfunction "IO42_35") (pintype "input"))
      (node (ref "U41") (pin "13") (pinfunction "#CS_13") (pintype "input"))
    )
    (net (code "40") (name "U11_UART0_RX") (class "Default")
      (node (ref "J5") (pin "5") (pinfunction "5_5") (pintype "input"))
      (node (ref "U11") (pin "36") (pinfunction "RXD0_36") (pintype "input"))
    )
    (net (code "41") (name "U11_UART0_TX") (class "Default")
      (node (ref "J5") (pin "3") (pinfunction "3_3") (pintype "input"))
      (node (ref "U11") (pin "37") (pinfunction "TXD0_37") (pintype "input"))
    )
    (net (code "42") (name "U27_USBD+") (class "Default")
      (node (ref "U11") (pin "14") (pinfunction "IO20_14") (pintype "input"))
      (node (ref "USB1") (pin "A6") (pinfunction "DP1_A6") (pintype "input"))
      (node (ref "USB1") (pin "B6") (pinfunction "DP2_B6") (pintype "input"))
    )
    (net (code "43") (name "U27_USBD-") (class "Default")
      (node (ref "U11") (pin "13") (pinfunction "IO19_13") (pintype "input"))
      (node (ref "USB1") (pin "A7") (pinfunction "DN1_A7") (pintype "input"))
      (node (ref "USB1") (pin "B7") (pinfunction "DN2_B7") (pintype "input"))
    )
    (net (code "44") (name "VCC") (class "Default")
      (node (ref "C2") (pin "2") (pinfunction "2_2") (pintype "input"))
      (node (ref "C22") (pin "1") (pinfunction "1_1") (pintype "input"))
      (node (ref "C23") (pin "2") (pinfunction "2_2") (pintype "input"))
      (node (ref "C3") (pin "2") (pinfunction "2_2") (pintype "input"))
      (node (ref "C4") (pin "2") (pinfunction "2_2") (pintype "input"))
      (node (ref "C5") (pin "1") (pinfunction "1_1") (pintype "input"))
      (node (ref "D1") (pin "1") (pinfunction "C_1") (pintype "input"))
      (node (ref "D2") (pin "1") (pinfunction "C_1") (pintype "input"))
      (node (ref "D3") (pin "1") (pinfunction "C_1") (pintype "input"))
      (node (ref "K1") (pin "4") (pinfunction "4_4") (pintype "input"))
      (node (ref "K2") (pin "4") (pinfunction "4_4") (pintype "input"))
      (node (ref "K3") (pin "4") (pinfunction "4_4") (pintype "input"))
      (node (ref "P28") (pin "2") (pinfunction "2_2") (pintype "input"))
      (node (ref "P31") (pin "1") (pinfunction "1_1") (pintype "input"))
      (node (ref "P32") (pin "1") (pinfunction "1_1") (pintype "input"))
      (node (ref "P33") (pin "1") (pinfunction "1_1") (pintype "input"))
      (node (ref "U1") (pin "4") (pinfunction "+VO_4") (pintype "input"))
      (node (ref "U23") (pin "3") (pinfunction "VIN_3") (pintype "input"))
      (node (ref "U32") (pin "9") (pinfunction "COM_9") (pintype "input"))
      (node (ref "USB1") (pin "A4") (pinfunction "VBUS_A4") (pintype "input"))
      (node (ref "USB1") (pin "A9") (pinfunction "VBUS_A9") (pintype "input"))
      (node (ref "USB1") (pin "B4") (pinfunction "VBUS_B4") (pintype "input"))
      (node (ref "USB1") (pin "B9") (pinfunction "VBUS_B9") (pintype "input"))
    )
    (net (code "45") (name "unconnected-(U11-IO1-Pad39)") (class "Default")
      (node (ref "U11") (pin "39") (pinfunction "IO1_39") (pintype "input+no_connect"))
    )
    (net (code "46") (name "unconnected-(U11-IO2-Pad38)") (class "Default")
      (node (ref "U11") (pin "38") (pinfunction "IO2_38") (pintype "input+no_connect"))
    )
    (net (code "47") (name "unconnected-(U11-IO3-Pad15)") (class "Default")
      (node (ref "U11") (pin "15") (pinfunction "IO3_15") (pintype "input+no_connect"))
    )
    (net (code "48") (name "unconnected-(U11-IO10-Pad18)") (class "Default")
      (node (ref "U11") (pin "18") (pinfunction "IO10_18") (pintype "input+no_connect"))
    )
    (net (code "49") (name "unconnected-(U11-IO11-Pad19)") (class "Default")
      (node (ref "U11") (pin "19") (pinfunction "IO11_19") (pintype "input+no_connect"))
    )
    (net (code "50") (name "unconnected-(U11-IO12-Pad20)") (class "Default")
      (node (ref "U11") (pin "20") (pinfunction "IO12_20") (pintype "input+no_connect"))
    )
    (net (code "51") (name "unconnected-(U11-IO13-Pad21)") (class "Default")
      (node (ref "U11") (pin "21") (pinfunction "IO13_21") (pintype "input+no_connect"))
    )
    (net (code "52") (name "unconnected-(U11-IO14-Pad22)") (class "Default")
      (node (ref "U11") (pin "22") (pinfunction "IO14_22") (pintype "input+no_connect"))
    )
    (net (code "53") (name "unconnected-(U11-IO18-Pad11)") (class "Default")
      (node (ref "U11") (pin "11") (pinfunction "IO18_11") (pintype "input+no_connect"))
    )
    (net (code "54") (name "unconnected-(U11-IO21-Pad23)") (class "Default")
      (node (ref "U11") (pin "23") (pinfunction "IO21_23") (pintype "input+no_connect"))
    )
    (net (code "55") (name "unconnected-(U11-IO35-Pad28)") (class "Default")
      (node (ref "U11") (pin "28") (pinfunction "IO35_28") (pintype "input+no_connect"))
    )
    (net (code "56") (name "unconnected-(U11-IO36-Pad29)") (class "Default")
      (node (ref "U11") (pin "29") (pinfunction "IO36_29") (pintype "input+no_connect"))
    )
    (net (code "57") (name "unconnected-(U11-IO37-Pad30)") (class "Default")
      (node (ref "U11") (pin "30") (pinfunction "IO37_30") (pintype "input+no_connect"))
    )
    (net (code "58") (name "unconnected-(U11-IO38-Pad31)") (class "Default")
      (node (ref "U11") (pin "31") (pinfunction "IO38_31") (pintype "input+no_connect"))
    )
    (net (code "59") (name "unconnected-(U11-IO45-Pad26)") (class "Default")
      (node (ref "U11") (pin "26") (pinfunction "IO45_26") (pintype "input+no_connect"))
    )
    (net (code "60") (name "unconnected-(U11-IO46-Pad16)") (class "Default")
      (node (ref "U11") (pin "16") (pinfunction "IO46_16") (pintype "input+no_connect"))
    )
    (net (code "61") (name "unconnected-(U11-IO47-Pad24)") (class "Default")
      (node (ref "U11") (pin "24") (pinfunction "IO47_24") (pintype "input+no_connect"))
    )
    (net (code "62") (name "unconnected-(U11-IO48-Pad25)") (class "Default")
      (node (ref "U11") (pin "25") (pinfunction "IO48_25") (pintype "input+no_connect"))
    )
    (net (code "63") (name "unconnected-(U32-7B-Pad7)") (class "Default")
      (node (ref "U32") (pin "7") (pinfunction "7B_7") (pintype "input+no_connect"))
    )
    (net (code "64") (name "unconnected-(U32-7C-Pad10)") (class "Default")
      (node (ref "U32") (pin "10") (pinfunction "7C_10") (pintype "input+no_connect"))
    )
    (net (code "65") (name "unconnected-(U41-#DRDY-Pad18)") (class "Default")
      (node (ref "U41") (pin "18") (pinfunction "#DRDY_18") (pintype "input+no_connect"))
    )
    (net (code "66") (name "unconnected-(U41-N.C-Pad17)") (class "Default")
      (node (ref "U41") (pin "17") (pinfunction "N.C_17") (pintype "input+no_connect"))
    )
    (net (code "67") (name "unconnected-(U61-NC-Pad1)") (class "Default")
      (node (ref "U61") (pin "1") (pinfunction "NC_1") (pintype "input+no_connect"))
    )
    (net (code "68") (name "unconnected-(U61-NC-Pad2)") (class "Default")
      (node (ref "U61") (pin "2") (pinfunction "NC_2") (pintype "input+no_connect"))
    )
    (net (code "69") (name "unconnected-(U61-NC-Pad3)") (class "Default")
      (node (ref "U61") (pin "3") (pinfunction "NC_3") (pintype "input+no_connect"))
    )
    (net (code "70") (name "unconnected-(U61-NC-Pad7)") (class "Default")
      (node (ref "U61") (pin "7") (pinfunction "NC_7") (pintype "input+no_connect"))
    )
  )
)
